# MK_IR_I2C.net
KiCad netlist of a schematic drawn in EasyEDA Pro
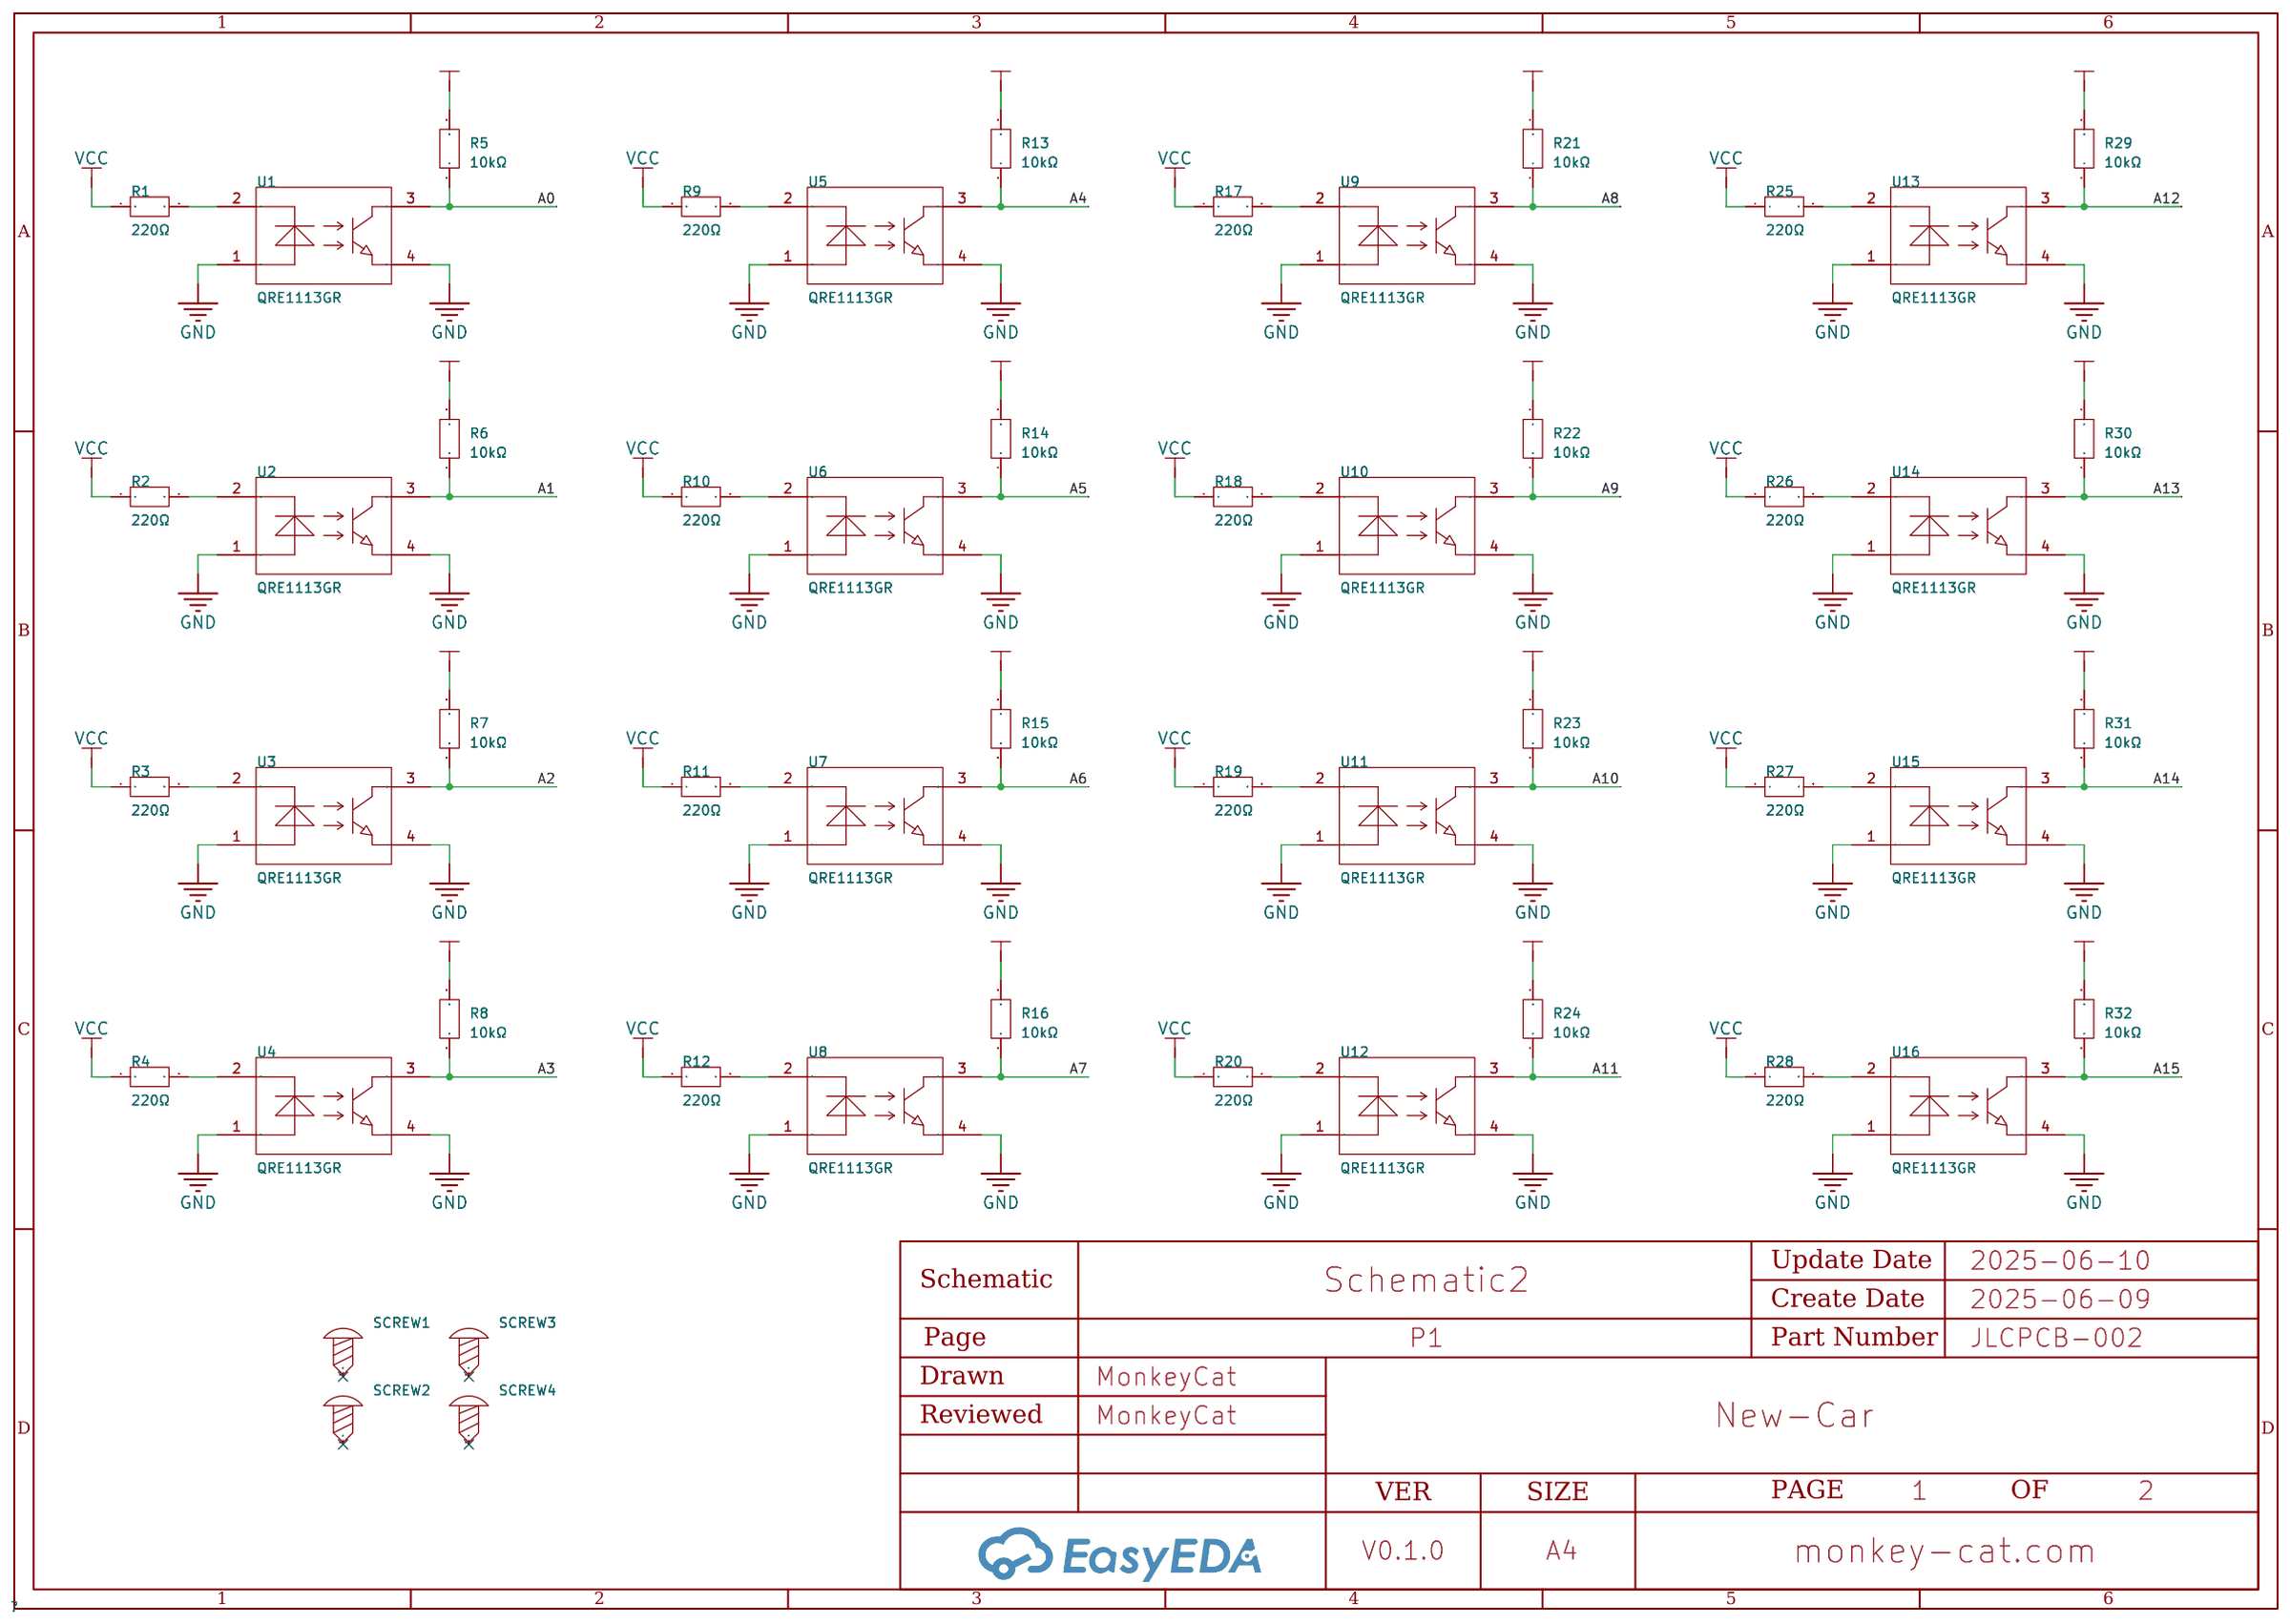
[diagram p0: P1]
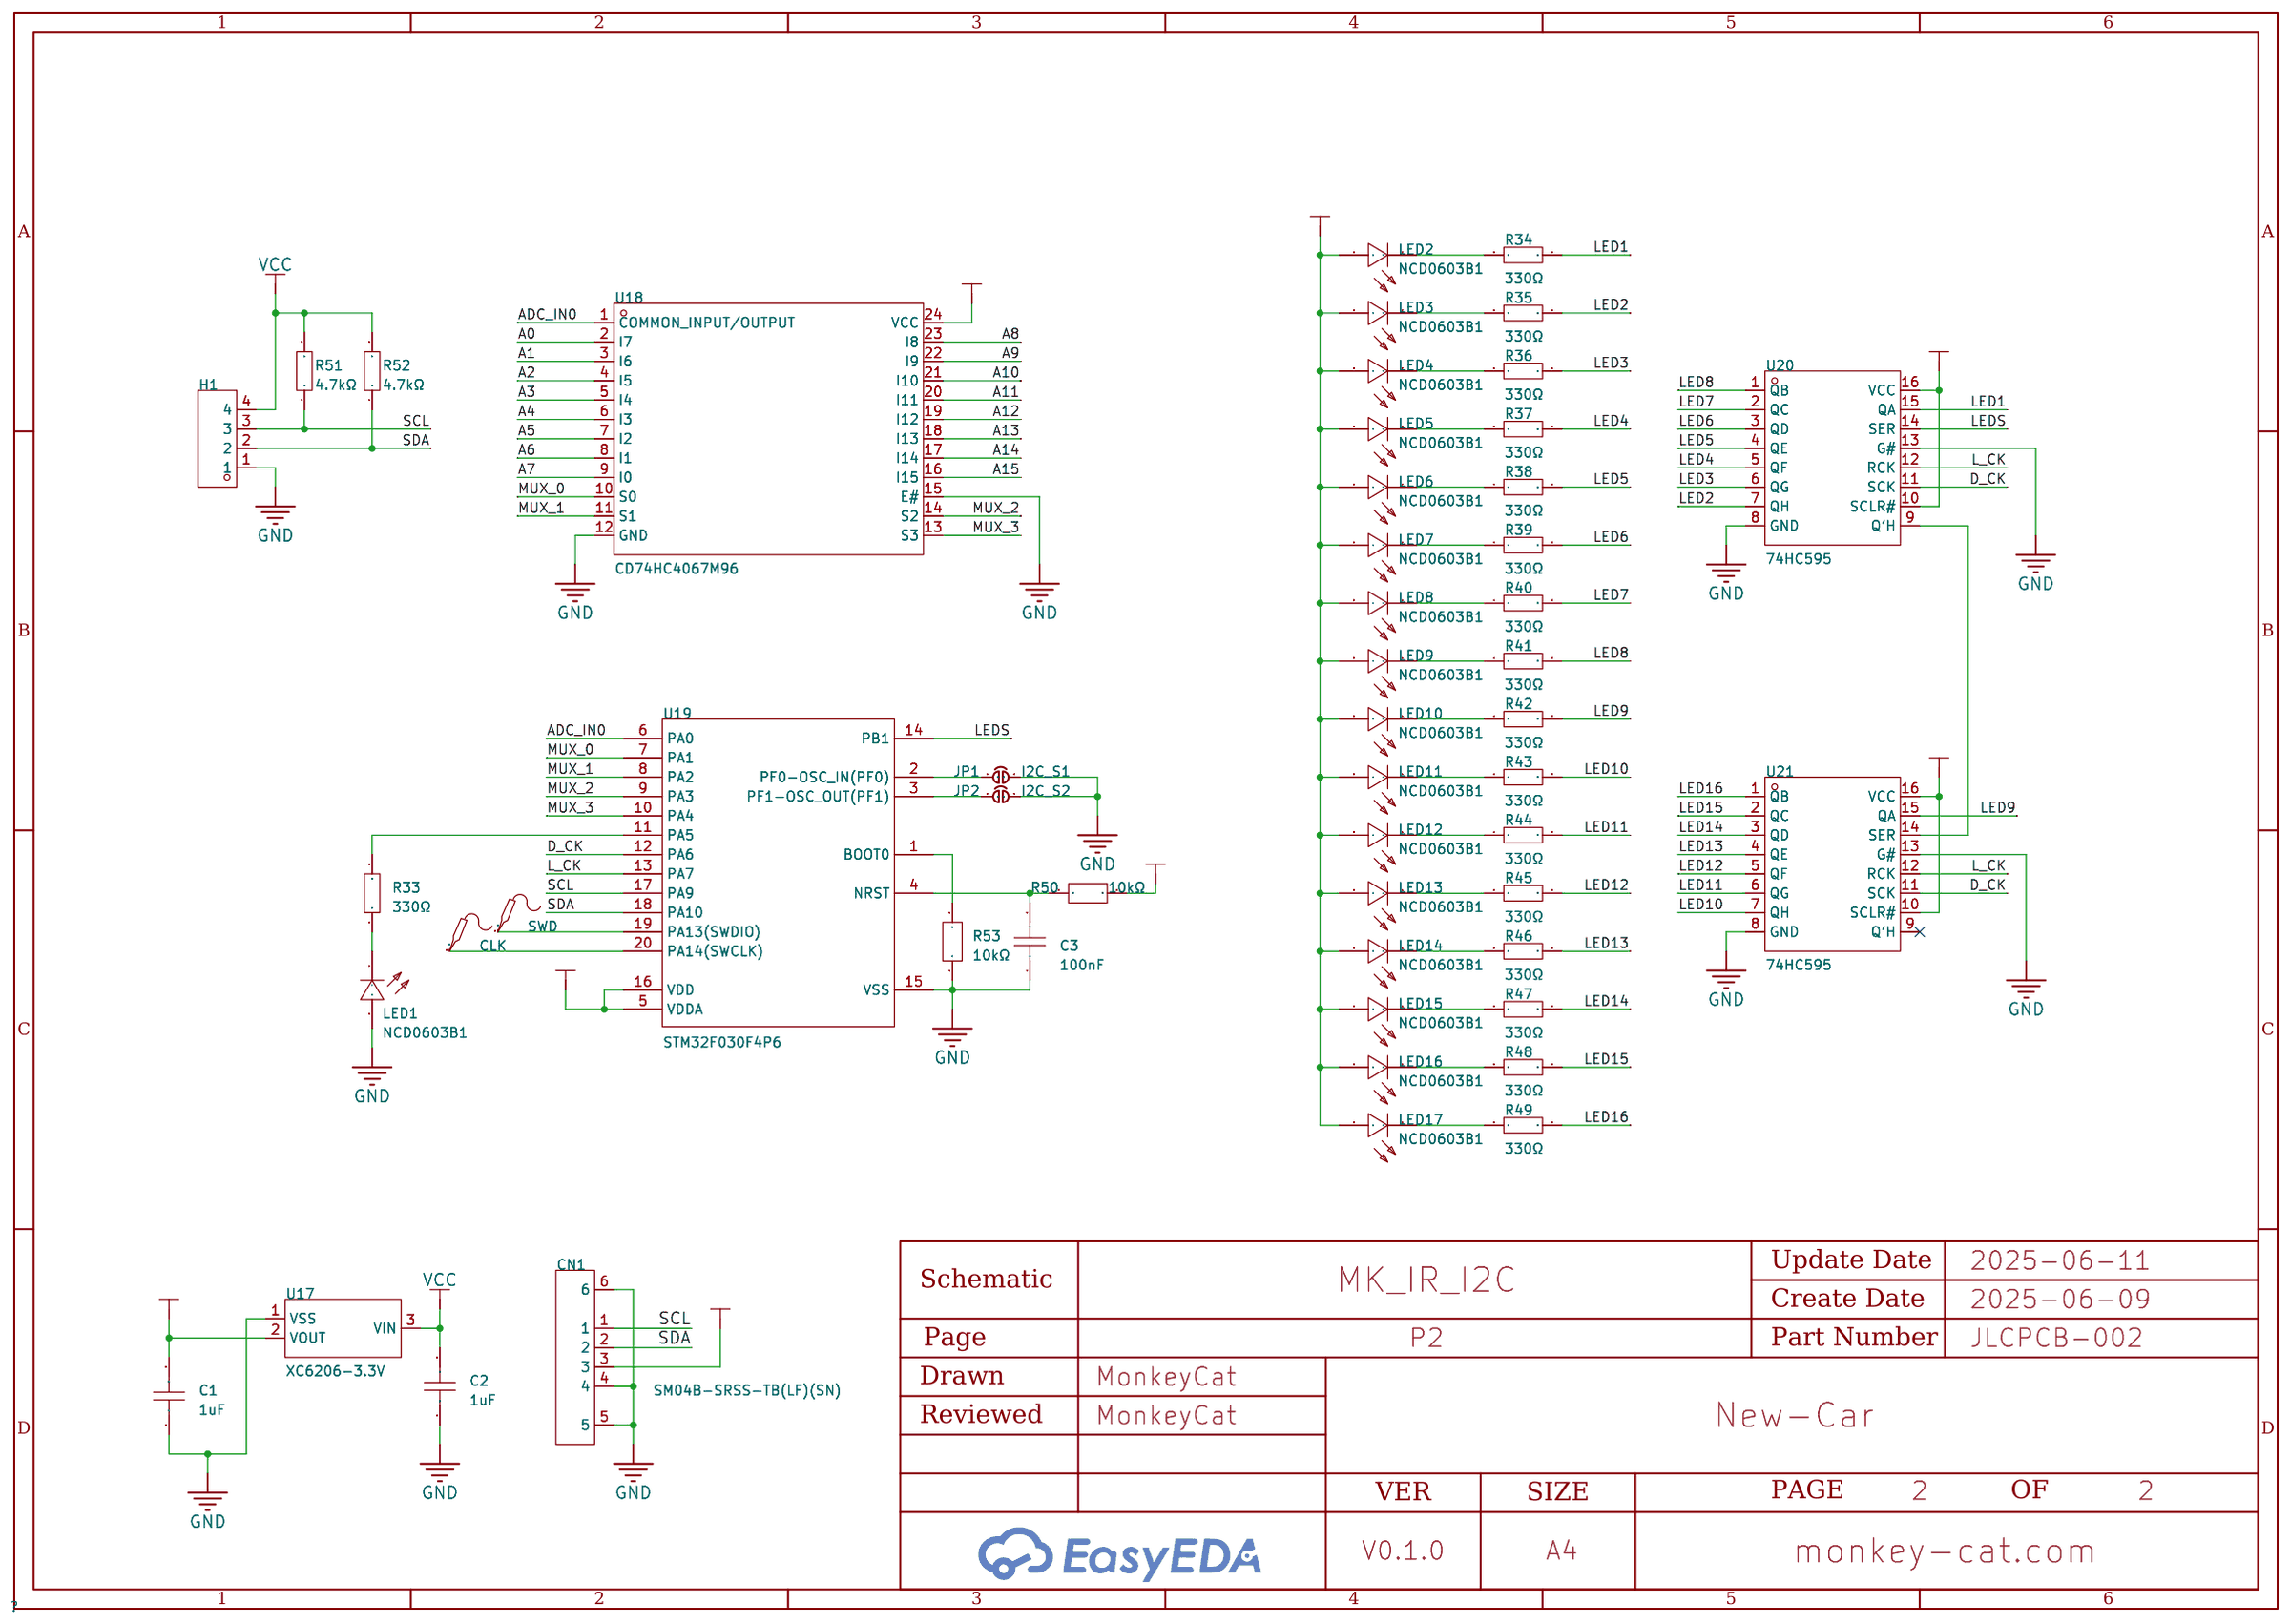
[diagram p1: P2]

(export (version "E")
  (design (tool "Eeschema 10.0.6"))
  (components
    (comp (ref "R1")
      (value "220Ω")
      (footprint "easyedapro:R0603")
      (fields (field (name "Manufacturer Part") "FRC0603F2200TS") (field (name "Manufacturer") "FOJAN(富捷)"))
      (libsource (lib "easyedapro") (part "FRC0603F2200TS"))
    )
    (comp (ref "R2")
      (value "220Ω")
      (footprint "easyedapro:R0603")
      (fields (field (name "Manufacturer Part") "FRC0603F2200TS") (field (name "Manufacturer") "FOJAN(富捷)"))
      (libsource (lib "easyedapro") (part "FRC0603F2200TS"))
    )
    (comp (ref "R3")
      (value "220Ω")
      (footprint "easyedapro:R0603")
      (fields (field (name "Manufacturer Part") "FRC0603F2200TS") (field (name "Manufacturer") "FOJAN(富捷)"))
      (libsource (lib "easyedapro") (part "FRC0603F2200TS"))
    )
    (comp (ref "R4")
      (value "220Ω")
      (footprint "easyedapro:R0603")
      (fields (field (name "Manufacturer Part") "FRC0603F2200TS") (field (name "Manufacturer") "FOJAN(富捷)"))
      (libsource (lib "easyedapro") (part "FRC0603F2200TS"))
    )
    (comp (ref "R5")
      (value "10kΩ")
      (footprint "easyedapro:R0603")
      (fields (field (name "Manufacturer Part") "FRC0603J103 TS") (field (name "Manufacturer") "FOJAN(富捷)"))
      (libsource (lib "easyedapro") (part "FRC0603J103TS"))
    )
    (comp (ref "R6")
      (value "10kΩ")
      (footprint "easyedapro:R0603")
      (fields (field (name "Manufacturer Part") "FRC0603J103 TS") (field (name "Manufacturer") "FOJAN(富捷)"))
      (libsource (lib "easyedapro") (part "FRC0603J103TS"))
    )
    (comp (ref "R7")
      (value "10kΩ")
      (footprint "easyedapro:R0603")
      (fields (field (name "Manufacturer Part") "FRC0603J103 TS") (field (name "Manufacturer") "FOJAN(富捷)"))
      (libsource (lib "easyedapro") (part "FRC0603J103TS"))
    )
    (comp (ref "R8")
      (value "10kΩ")
      (footprint "easyedapro:R0603")
      (fields (field (name "Manufacturer Part") "FRC0603J103 TS") (field (name "Manufacturer") "FOJAN(富捷)"))
      (libsource (lib "easyedapro") (part "FRC0603J103TS"))
    )
    (comp (ref "R9")
      (value "220Ω")
      (footprint "easyedapro:R0603")
      (fields (field (name "Manufacturer Part") "FRC0603F2200TS") (field (name "Manufacturer") "FOJAN(富捷)"))
      (libsource (lib "easyedapro") (part "FRC0603F2200TS"))
    )
    (comp (ref "R10")
      (value "220Ω")
      (footprint "easyedapro:R0603")
      (fields (field (name "Manufacturer Part") "FRC0603F2200TS") (field (name "Manufacturer") "FOJAN(富捷)"))
      (libsource (lib "easyedapro") (part "FRC0603F2200TS"))
    )
    (comp (ref "R11")
      (value "220Ω")
      (footprint "easyedapro:R0603")
      (fields (field (name "Manufacturer Part") "FRC0603F2200TS") (field (name "Manufacturer") "FOJAN(富捷)"))
      (libsource (lib "easyedapro") (part "FRC0603F2200TS"))
    )
    (comp (ref "R12")
      (value "220Ω")
      (footprint "easyedapro:R0603")
      (fields (field (name "Manufacturer Part") "FRC0603F2200TS") (field (name "Manufacturer") "FOJAN(富捷)"))
      (libsource (lib "easyedapro") (part "FRC0603F2200TS"))
    )
    (comp (ref "R13")
      (value "10kΩ")
      (footprint "easyedapro:R0603")
      (fields (field (name "Manufacturer Part") "FRC0603J103 TS") (field (name "Manufacturer") "FOJAN(富捷)"))
      (libsource (lib "easyedapro") (part "FRC0603J103TS"))
    )
    (comp (ref "R14")
      (value "10kΩ")
      (footprint "easyedapro:R0603")
      (fields (field (name "Manufacturer Part") "FRC0603J103 TS") (field (name "Manufacturer") "FOJAN(富捷)"))
      (libsource (lib "easyedapro") (part "FRC0603J103TS"))
    )
    (comp (ref "R15")
      (value "10kΩ")
      (footprint "easyedapro:R0603")
      (fields (field (name "Manufacturer Part") "FRC0603J103 TS") (field (name "Manufacturer") "FOJAN(富捷)"))
      (libsource (lib "easyedapro") (part "FRC0603J103TS"))
    )
    (comp (ref "R16")
      (value "10kΩ")
      (footprint "easyedapro:R0603")
      (fields (field (name "Manufacturer Part") "FRC0603J103 TS") (field (name "Manufacturer") "FOJAN(富捷)"))
      (libsource (lib "easyedapro") (part "FRC0603J103TS"))
    )
    (comp (ref "R17")
      (value "220Ω")
      (footprint "easyedapro:R0603")
      (fields (field (name "Manufacturer Part") "FRC0603F2200TS") (field (name "Manufacturer") "FOJAN(富捷)"))
      (libsource (lib "easyedapro") (part "FRC0603F2200TS"))
    )
    (comp (ref "R18")
      (value "220Ω")
      (footprint "easyedapro:R0603")
      (fields (field (name "Manufacturer Part") "FRC0603F2200TS") (field (name "Manufacturer") "FOJAN(富捷)"))
      (libsource (lib "easyedapro") (part "FRC0603F2200TS"))
    )
    (comp (ref "R19")
      (value "220Ω")
      (footprint "easyedapro:R0603")
      (fields (field (name "Manufacturer Part") "FRC0603F2200TS") (field (name "Manufacturer") "FOJAN(富捷)"))
      (libsource (lib "easyedapro") (part "FRC0603F2200TS"))
    )
    (comp (ref "R20")
      (value "220Ω")
      (footprint "easyedapro:R0603")
      (fields (field (name "Manufacturer Part") "FRC0603F2200TS") (field (name "Manufacturer") "FOJAN(富捷)"))
      (libsource (lib "easyedapro") (part "FRC0603F2200TS"))
    )
    (comp (ref "R21")
      (value "10kΩ")
      (footprint "easyedapro:R0603")
      (fields (field (name "Manufacturer Part") "FRC0603J103 TS") (field (name "Manufacturer") "FOJAN(富捷)"))
      (libsource (lib "easyedapro") (part "FRC0603J103TS"))
    )
    (comp (ref "R22")
      (value "10kΩ")
      (footprint "easyedapro:R0603")
      (fields (field (name "Manufacturer Part") "FRC0603J103 TS") (field (name "Manufacturer") "FOJAN(富捷)"))
      (libsource (lib "easyedapro") (part "FRC0603J103TS"))
    )
    (comp (ref "R23")
      (value "10kΩ")
      (footprint "easyedapro:R0603")
      (fields (field (name "Manufacturer Part") "FRC0603J103 TS") (field (name "Manufacturer") "FOJAN(富捷)"))
      (libsource (lib "easyedapro") (part "FRC0603J103TS"))
    )
    (comp (ref "R24")
      (value "10kΩ")
      (footprint "easyedapro:R0603")
      (fields (field (name "Manufacturer Part") "FRC0603J103 TS") (field (name "Manufacturer") "FOJAN(富捷)"))
      (libsource (lib "easyedapro") (part "FRC0603J103TS"))
    )
    (comp (ref "R25")
      (value "220Ω")
      (footprint "easyedapro:R0603")
      (fields (field (name "Manufacturer Part") "FRC0603F2200TS") (field (name "Manufacturer") "FOJAN(富捷)"))
      (libsource (lib "easyedapro") (part "FRC0603F2200TS"))
    )
    (comp (ref "R26")
      (value "220Ω")
      (footprint "easyedapro:R0603")
      (fields (field (name "Manufacturer Part") "FRC0603F2200TS") (field (name "Manufacturer") "FOJAN(富捷)"))
      (libsource (lib "easyedapro") (part "FRC0603F2200TS"))
    )
    (comp (ref "R27")
      (value "220Ω")
      (footprint "easyedapro:R0603")
      (fields (field (name "Manufacturer Part") "FRC0603F2200TS") (field (name "Manufacturer") "FOJAN(富捷)"))
      (libsource (lib "easyedapro") (part "FRC0603F2200TS"))
    )
    (comp (ref "R28")
      (value "220Ω")
      (footprint "easyedapro:R0603")
      (fields (field (name "Manufacturer Part") "FRC0603F2200TS") (field (name "Manufacturer") "FOJAN(富捷)"))
      (libsource (lib "easyedapro") (part "FRC0603F2200TS"))
    )
    (comp (ref "R29")
      (value "10kΩ")
      (footprint "easyedapro:R0603")
      (fields (field (name "Manufacturer Part") "FRC0603J103 TS") (field (name "Manufacturer") "FOJAN(富捷)"))
      (libsource (lib "easyedapro") (part "FRC0603J103TS"))
    )
    (comp (ref "R30")
      (value "10kΩ")
      (footprint "easyedapro:R0603")
      (fields (field (name "Manufacturer Part") "FRC0603J103 TS") (field (name "Manufacturer") "FOJAN(富捷)"))
      (libsource (lib "easyedapro") (part "FRC0603J103TS"))
    )
    (comp (ref "R31")
      (value "10kΩ")
      (footprint "easyedapro:R0603")
      (fields (field (name "Manufacturer Part") "FRC0603J103 TS") (field (name "Manufacturer") "FOJAN(富捷)"))
      (libsource (lib "easyedapro") (part "FRC0603J103TS"))
    )
    (comp (ref "R32")
      (value "10kΩ")
      (footprint "easyedapro:R0603")
      (fields (field (name "Manufacturer Part") "FRC0603J103 TS") (field (name "Manufacturer") "FOJAN(富捷)"))
      (libsource (lib "easyedapro") (part "FRC0603J103TS"))
    )
    (comp (ref "SCREW1")
      (value "~")
      (footprint "easyedapro:Screw-Hole-M3")
      (libsource (lib "easyedapro") (part "Screw-Hole"))
    )
    (comp (ref "SCREW2")
      (value "~")
      (footprint "easyedapro:Screw-Hole-M3")
      (libsource (lib "easyedapro") (part "Screw-Hole"))
    )
    (comp (ref "SCREW3")
      (value "~")
      (footprint "easyedapro:Screw-Hole-M3")
      (libsource (lib "easyedapro") (part "Screw-Hole"))
    )
    (comp (ref "SCREW4")
      (value "~")
      (footprint "easyedapro:Screw-Hole-M3")
      (libsource (lib "easyedapro") (part "Screw-Hole"))
    )
    (comp (ref "U1")
      (value "QRE1113GR")
      (footprint "easyedapro:OPTO-SMD_QRE1113GR")
      (description "Sensing Distance:1mm Collector Current (Max):20mA")
      (fields (field (name "Manufacturer") "onsemi(安森美)"))
      (libsource (lib "easyedapro") (part "QRE1113GR"))
    )
    (comp (ref "U2")
      (value "QRE1113GR")
      (footprint "easyedapro:OPTO-SMD_QRE1113GR")
      (description "Sensing Distance:1mm Collector Current (Max):20mA")
      (fields (field (name "Manufacturer") "onsemi(安森美)"))
      (libsource (lib "easyedapro") (part "QRE1113GR"))
    )
    (comp (ref "U3")
      (value "QRE1113GR")
      (footprint "easyedapro:OPTO-SMD_QRE1113GR")
      (description "Sensing Distance:1mm Collector Current (Max):20mA")
      (fields (field (name "Manufacturer") "onsemi(安森美)"))
      (libsource (lib "easyedapro") (part "QRE1113GR"))
    )
    (comp (ref "U4")
      (value "QRE1113GR")
      (footprint "easyedapro:OPTO-SMD_QRE1113GR")
      (description "Sensing Distance:1mm Collector Current (Max):20mA")
      (fields (field (name "Manufacturer") "onsemi(安森美)"))
      (libsource (lib "easyedapro") (part "QRE1113GR"))
    )
    (comp (ref "U5")
      (value "QRE1113GR")
      (footprint "easyedapro:OPTO-SMD_QRE1113GR")
      (description "Sensing Distance:1mm Collector Current (Max):20mA")
      (fields (field (name "Manufacturer") "onsemi(安森美)"))
      (libsource (lib "easyedapro") (part "QRE1113GR"))
    )
    (comp (ref "U6")
      (value "QRE1113GR")
      (footprint "easyedapro:OPTO-SMD_QRE1113GR")
      (description "Sensing Distance:1mm Collector Current (Max):20mA")
      (fields (field (name "Manufacturer") "onsemi(安森美)"))
      (libsource (lib "easyedapro") (part "QRE1113GR"))
    )
    (comp (ref "U7")
      (value "QRE1113GR")
      (footprint "easyedapro:OPTO-SMD_QRE1113GR")
      (description "Sensing Distance:1mm Collector Current (Max):20mA")
      (fields (field (name "Manufacturer") "onsemi(安森美)"))
      (libsource (lib "easyedapro") (part "QRE1113GR"))
    )
    (comp (ref "U8")
      (value "QRE1113GR")
      (footprint "easyedapro:OPTO-SMD_QRE1113GR")
      (description "Sensing Distance:1mm Collector Current (Max):20mA")
      (fields (field (name "Manufacturer") "onsemi(安森美)"))
      (libsource (lib "easyedapro") (part "QRE1113GR"))
    )
    (comp (ref "U9")
      (value "QRE1113GR")
      (footprint "easyedapro:OPTO-SMD_QRE1113GR")
      (description "Sensing Distance:1mm Collector Current (Max):20mA")
      (fields (field (name "Manufacturer") "onsemi(安森美)"))
      (libsource (lib "easyedapro") (part "QRE1113GR"))
    )
    (comp (ref "U10")
      (value "QRE1113GR")
      (footprint "easyedapro:OPTO-SMD_QRE1113GR")
      (description "Sensing Distance:1mm Collector Current (Max):20mA")
      (fields (field (name "Manufacturer") "onsemi(安森美)"))
      (libsource (lib "easyedapro") (part "QRE1113GR"))
    )
    (comp (ref "U11")
      (value "QRE1113GR")
      (footprint "easyedapro:OPTO-SMD_QRE1113GR")
      (description "Sensing Distance:1mm Collector Current (Max):20mA")
      (fields (field (name "Manufacturer") "onsemi(安森美)"))
      (libsource (lib "easyedapro") (part "QRE1113GR"))
    )
    (comp (ref "U12")
      (value "QRE1113GR")
      (footprint "easyedapro:OPTO-SMD_QRE1113GR")
      (description "Sensing Distance:1mm Collector Current (Max):20mA")
      (fields (field (name "Manufacturer") "onsemi(安森美)"))
      (libsource (lib "easyedapro") (part "QRE1113GR"))
    )
    (comp (ref "U13")
      (value "QRE1113GR")
      (footprint "easyedapro:OPTO-SMD_QRE1113GR")
      (description "Sensing Distance:1mm Collector Current (Max):20mA")
      (fields (field (name "Manufacturer") "onsemi(安森美)"))
      (libsource (lib "easyedapro") (part "QRE1113GR"))
    )
    (comp (ref "U14")
      (value "QRE1113GR")
      (footprint "easyedapro:OPTO-SMD_QRE1113GR")
      (description "Sensing Distance:1mm Collector Current (Max):20mA")
      (fields (field (name "Manufacturer") "onsemi(安森美)"))
      (libsource (lib "easyedapro") (part "QRE1113GR"))
    )
    (comp (ref "U15")
      (value "QRE1113GR")
      (footprint "easyedapro:OPTO-SMD_QRE1113GR")
      (description "Sensing Distance:1mm Collector Current (Max):20mA")
      (fields (field (name "Manufacturer") "onsemi(安森美)"))
      (libsource (lib "easyedapro") (part "QRE1113GR"))
    )
    (comp (ref "U16")
      (value "QRE1113GR")
      (footprint "easyedapro:OPTO-SMD_QRE1113GR")
      (description "Sensing Distance:1mm Collector Current (Max):20mA")
      (fields (field (name "Manufacturer") "onsemi(安森美)"))
      (libsource (lib "easyedapro") (part "QRE1113GR"))
    )
    (comp (ref "C1")
      (value "1uF")
      (footprint "easyedapro:C0603")
      (fields
        (field (name "Manufacturer Part") "CL10A105KB8NNNC")
        (field (name "Manufacturer") "SAMSUNG(三星)")
      )
      (libsource (lib "easyedapro") (part "CL10A105KB8NNNC"))
    )
    (comp (ref "C2")
      (value "1uF")
      (footprint "easyedapro:C0603")
      (fields
        (field (name "Manufacturer Part") "CL10A105KB8NNNC")
        (field (name "Manufacturer") "SAMSUNG(三星)")
      )
      (libsource (lib "easyedapro") (part "CL10A105KB8NNNC"))
    )
    (comp (ref "C3")
      (value "100nF")
      (footprint "easyedapro:C0603")
      (fields
        (field (name "Manufacturer Part") "CC0603KRX7R9BB104")
        (field (name "Manufacturer") "YAGEO(国巨)")
      )
      (libsource (lib "easyedapro") (part "CC0603KRX7R9BB104"))
    )
    (comp (ref "CLK")
      (value "~")
      (footprint "easyedapro:Test-Point-0.5mm")
      (description "Test Point 测试点")
      (libsource (lib "easyedapro") (part "Test-Point"))
    )
    (comp (ref "CN1")
      (value "SM04B-SRSS-TB(LF)(SN)")
      (footprint "easyedapro:CONN-SMD_4P-P1.00_SM04B-SRSS-TB-LF-SN")
      (fields (field (name "Manufacturer") "JST"))
      (libsource (lib "easyedapro") (part "SM04B-SRSS-TB (LF)(SN)"))
    )
    (comp (ref "H1")
      (value "~")
      (footprint "easyedapro:HDR-TH_4P-P2.54-V-M")
      (libsource (lib "easyedapro") (part "PZ254V-11-04P"))
    )
    (comp (ref "JP1")
      (value "I2C_S1")
      (footprint "easyedapro:SOLDER JUMPER")
      (libsource (lib "easyedapro") (part "Solder Jumper"))
    )
    (comp (ref "JP2")
      (value "I2C_S2")
      (footprint "easyedapro:SOLDER JUMPER")
      (libsource (lib "easyedapro") (part "Solder Jumper"))
    )
    (comp (ref "LED1")
      (value "NCD0603B1")
      (footprint "easyedapro:LED0603-RD")
      (fields (field (name "Manufacturer") "国星光电"))
      (libsource (lib "easyedapro") (part "FC-DA1608BK-470H10"))
    )
    (comp (ref "LED2")
      (value "NCD0603B1")
      (footprint "easyedapro:LED0603-RD")
      (fields (field (name "Manufacturer") "国星光电"))
      (libsource (lib "easyedapro") (part "FC-DA1608BK-470H10"))
    )
    (comp (ref "LED3")
      (value "NCD0603B1")
      (footprint "easyedapro:LED0603-RD")
      (fields (field (name "Manufacturer") "国星光电"))
      (libsource (lib "easyedapro") (part "FC-DA1608BK-470H10"))
    )
    (comp (ref "LED4")
      (value "NCD0603B1")
      (footprint "easyedapro:LED0603-RD")
      (fields (field (name "Manufacturer") "国星光电"))
      (libsource (lib "easyedapro") (part "FC-DA1608BK-470H10"))
    )
    (comp (ref "LED5")
      (value "NCD0603B1")
      (footprint "easyedapro:LED0603-RD")
      (fields (field (name "Manufacturer") "国星光电"))
      (libsource (lib "easyedapro") (part "FC-DA1608BK-470H10"))
    )
    (comp (ref "LED6")
      (value "NCD0603B1")
      (footprint "easyedapro:LED0603-RD")
      (fields (field (name "Manufacturer") "国星光电"))
      (libsource (lib "easyedapro") (part "FC-DA1608BK-470H10"))
    )
    (comp (ref "LED7")
      (value "NCD0603B1")
      (footprint "easyedapro:LED0603-RD")
      (fields (field (name "Manufacturer") "国星光电"))
      (libsource (lib "easyedapro") (part "FC-DA1608BK-470H10"))
    )
    (comp (ref "LED8")
      (value "NCD0603B1")
      (footprint "easyedapro:LED0603-RD")
      (fields (field (name "Manufacturer") "国星光电"))
      (libsource (lib "easyedapro") (part "FC-DA1608BK-470H10"))
    )
    (comp (ref "LED9")
      (value "NCD0603B1")
      (footprint "easyedapro:LED0603-RD")
      (fields (field (name "Manufacturer") "国星光电"))
      (libsource (lib "easyedapro") (part "FC-DA1608BK-470H10"))
    )
    (comp (ref "LED10")
      (value "NCD0603B1")
      (footprint "easyedapro:LED0603-RD")
      (fields (field (name "Manufacturer") "国星光电"))
      (libsource (lib "easyedapro") (part "FC-DA1608BK-470H10"))
    )
    (comp (ref "LED11")
      (value "NCD0603B1")
      (footprint "easyedapro:LED0603-RD")
      (fields (field (name "Manufacturer") "国星光电"))
      (libsource (lib "easyedapro") (part "FC-DA1608BK-470H10"))
    )
    (comp (ref "LED12")
      (value "NCD0603B1")
      (footprint "easyedapro:LED0603-RD")
      (fields (field (name "Manufacturer") "国星光电"))
      (libsource (lib "easyedapro") (part "FC-DA1608BK-470H10"))
    )
    (comp (ref "LED13")
      (value "NCD0603B1")
      (footprint "easyedapro:LED0603-RD")
      (fields (field (name "Manufacturer") "国星光电"))
      (libsource (lib "easyedapro") (part "FC-DA1608BK-470H10"))
    )
    (comp (ref "LED14")
      (value "NCD0603B1")
      (footprint "easyedapro:LED0603-RD")
      (fields (field (name "Manufacturer") "国星光电"))
      (libsource (lib "easyedapro") (part "FC-DA1608BK-470H10"))
    )
    (comp (ref "LED15")
      (value "NCD0603B1")
      (footprint "easyedapro:LED0603-RD")
      (fields (field (name "Manufacturer") "国星光电"))
      (libsource (lib "easyedapro") (part "FC-DA1608BK-470H10"))
    )
    (comp (ref "LED16")
      (value "NCD0603B1")
      (footprint "easyedapro:LED0603-RD")
      (fields (field (name "Manufacturer") "国星光电"))
      (libsource (lib "easyedapro") (part "FC-DA1608BK-470H10"))
    )
    (comp (ref "LED17")
      (value "NCD0603B1")
      (footprint "easyedapro:LED0603-RD")
      (fields (field (name "Manufacturer") "国星光电"))
      (libsource (lib "easyedapro") (part "FC-DA1608BK-470H10"))
    )
    (comp (ref "R33")
      (value "330Ω")
      (footprint "easyedapro:R0603")
      (fields
        (field (name "Manufacturer Part") "0603WAF3300T5E")
        (field (name "Manufacturer") "UNI-ROYAL(厚声)")
      )
      (libsource (lib "easyedapro") (part "0603WAF3300T5E"))
    )
    (comp (ref "R34")
      (value "330Ω")
      (footprint "easyedapro:R0603")
      (fields
        (field (name "Manufacturer Part") "0603WAF3300T5E")
        (field (name "Manufacturer") "UNI-ROYAL(厚声)")
      )
      (libsource (lib "easyedapro") (part "0603WAF3300T5E"))
    )
    (comp (ref "R35")
      (value "330Ω")
      (footprint "easyedapro:R0603")
      (fields
        (field (name "Manufacturer Part") "0603WAF3300T5E")
        (field (name "Manufacturer") "UNI-ROYAL(厚声)")
      )
      (libsource (lib "easyedapro") (part "0603WAF3300T5E"))
    )
    (comp (ref "R36")
      (value "330Ω")
      (footprint "easyedapro:R0603")
      (fields
        (field (name "Manufacturer Part") "0603WAF3300T5E")
        (field (name "Manufacturer") "UNI-ROYAL(厚声)")
      )
      (libsource (lib "easyedapro") (part "0603WAF3300T5E"))
    )
    (comp (ref "R37")
      (value "330Ω")
      (footprint "easyedapro:R0603")
      (fields
        (field (name "Manufacturer Part") "0603WAF3300T5E")
        (field (name "Manufacturer") "UNI-ROYAL(厚声)")
      )
      (libsource (lib "easyedapro") (part "0603WAF3300T5E"))
    )
    (comp (ref "R38")
      (value "330Ω")
      (footprint "easyedapro:R0603")
      (fields
        (field (name "Manufacturer Part") "0603WAF3300T5E")
        (field (name "Manufacturer") "UNI-ROYAL(厚声)")
      )
      (libsource (lib "easyedapro") (part "0603WAF3300T5E"))
    )
    (comp (ref "R39")
      (value "330Ω")
      (footprint "easyedapro:R0603")
      (fields
        (field (name "Manufacturer Part") "0603WAF3300T5E")
        (field (name "Manufacturer") "UNI-ROYAL(厚声)")
      )
      (libsource (lib "easyedapro") (part "0603WAF3300T5E"))
    )
    (comp (ref "R40")
      (value "330Ω")
      (footprint "easyedapro:R0603")
      (fields
        (field (name "Manufacturer Part") "0603WAF3300T5E")
        (field (name "Manufacturer") "UNI-ROYAL(厚声)")
      )
      (libsource (lib "easyedapro") (part "0603WAF3300T5E"))
    )
    (comp (ref "R41")
      (value "330Ω")
      (footprint "easyedapro:R0603")
      (fields
        (field (name "Manufacturer Part") "0603WAF3300T5E")
        (field (name "Manufacturer") "UNI-ROYAL(厚声)")
      )
      (libsource (lib "easyedapro") (part "0603WAF3300T5E"))
    )
    (comp (ref "R42")
      (value "330Ω")
      (footprint "easyedapro:R0603")
      (fields
        (field (name "Manufacturer Part") "0603WAF3300T5E")
        (field (name "Manufacturer") "UNI-ROYAL(厚声)")
      )
      (libsource (lib "easyedapro") (part "0603WAF3300T5E"))
    )
    (comp (ref "R43")
      (value "330Ω")
      (footprint "easyedapro:R0603")
      (fields
        (field (name "Manufacturer Part") "0603WAF3300T5E")
        (field (name "Manufacturer") "UNI-ROYAL(厚声)")
      )
      (libsource (lib "easyedapro") (part "0603WAF3300T5E"))
    )
    (comp (ref "R44")
      (value "330Ω")
      (footprint "easyedapro:R0603")
      (fields
        (field (name "Manufacturer Part") "0603WAF3300T5E")
        (field (name "Manufacturer") "UNI-ROYAL(厚声)")
      )
      (libsource (lib "easyedapro") (part "0603WAF3300T5E"))
    )
    (comp (ref "R45")
      (value "330Ω")
      (footprint "easyedapro:R0603")
      (fields
        (field (name "Manufacturer Part") "0603WAF3300T5E")
        (field (name "Manufacturer") "UNI-ROYAL(厚声)")
      )
      (libsource (lib "easyedapro") (part "0603WAF3300T5E"))
    )
    (comp (ref "R46")
      (value "330Ω")
      (footprint "easyedapro:R0603")
      (fields
        (field (name "Manufacturer Part") "0603WAF3300T5E")
        (field (name "Manufacturer") "UNI-ROYAL(厚声)")
      )
      (libsource (lib "easyedapro") (part "0603WAF3300T5E"))
    )
    (comp (ref "R47")
      (value "330Ω")
      (footprint "easyedapro:R0603")
      (fields
        (field (name "Manufacturer Part") "0603WAF3300T5E")
        (field (name "Manufacturer") "UNI-ROYAL(厚声)")
      )
      (libsource (lib "easyedapro") (part "0603WAF3300T5E"))
    )
    (comp (ref "R48")
      (value "330Ω")
      (footprint "easyedapro:R0603")
      (fields
        (field (name "Manufacturer Part") "0603WAF3300T5E")
        (field (name "Manufacturer") "UNI-ROYAL(厚声)")
      )
      (libsource (lib "easyedapro") (part "0603WAF3300T5E"))
    )
    (comp (ref "R49")
      (value "330Ω")
      (footprint "easyedapro:R0603")
      (fields
        (field (name "Manufacturer Part") "0603WAF3300T5E")
        (field (name "Manufacturer") "UNI-ROYAL(厚声)")
      )
      (libsource (lib "easyedapro") (part "0603WAF3300T5E"))
    )
    (comp (ref "R50")
      (value "10kΩ")
      (footprint "easyedapro:R0603")
      (fields (field (name "Manufacturer Part") "FRC0603J103 TS") (field (name "Manufacturer") "FOJAN(富捷)"))
      (libsource (lib "easyedapro") (part "FRC0603J103TS"))
    )
    (comp (ref "R51")
      (value "4.7kΩ")
      (footprint "easyedapro:R0603")
      (fields (field (name "Manufacturer Part") "RC0603FR-074K7L") (field (name "Manufacturer") "YAGEO(国巨)"))
      (libsource (lib "easyedapro") (part "RC0603FR-074K7L"))
    )
    (comp (ref "R52")
      (value "4.7kΩ")
      (footprint "easyedapro:R0603")
      (fields (field (name "Manufacturer Part") "RC0603FR-074K7L") (field (name "Manufacturer") "YAGEO(国巨)"))
      (libsource (lib "easyedapro") (part "RC0603FR-074K7L"))
    )
    (comp (ref "R53")
      (value "10kΩ")
      (footprint "easyedapro:R0603")
      (fields (field (name "Manufacturer Part") "FRC0603J103 TS") (field (name "Manufacturer") "FOJAN(富捷)"))
      (libsource (lib "easyedapro") (part "FRC0603J103TS"))
    )
    (comp (ref "SWD")
      (value "~")
      (footprint "easyedapro:Test-Point-0.5mm")
      (description "Test Point 测试点")
      (libsource (lib "easyedapro") (part "Test-Point"))
    )
    (comp (ref "U17")
      (value "XC6206-3.3V")
      (footprint "easyedapro:SOT-23-3_L2.9-W1.3-P0.95-LS2.4-BR")
      (fields (field (name "Manufacturer") "YONGYUTAI(永裕泰)"))
      (libsource (lib "easyedapro") (part "XC6206-3.3V_C3015484"))
    )
    (comp (ref "U18")
      (value "CD74HC4067M96")
      (footprint "easyedapro:SOIC-24_L15.4-W7.5-P1.27-LS10.3-BL")
      (fields (field (name "Manufacturer") "TI(德州仪器)"))
      (libsource (lib "easyedapro") (part "CD74HC4067M96"))
    )
    (comp (ref "U19")
      (value "STM32F030F4P6")
      (footprint "easyedapro:TSSOP-20_L6.5-W4.4-P0.65-LS6.4-BL")
      (fields (field (name "Manufacturer") "ST(意法半导体)"))
      (libsource (lib "easyedapro") (part "STM32F030F4P6"))
    )
    (comp (ref "U20")
      (value "74HC595")
      (footprint "easyedapro:SOP-16_L9.9-W3.9-P1.27-LS6.0-BL")
      (fields (field (name "Manufacturer") "GR(国睿)"))
      (libsource (lib "easyedapro") (part "74HC595"))
    )
    (comp (ref "U21")
      (value "74HC595")
      (footprint "easyedapro:SOP-16_L9.9-W3.9-P1.27-LS6.0-BL")
      (fields (field (name "Manufacturer") "GR(国睿)"))
      (libsource (lib "easyedapro") (part "74HC595"))
    )
  )
  (nets
    (net (code "1") (name "+3V3") (class "Default")
      (node (ref "C1") (pin "2") (pinfunction "2_2") (pintype "unspecified"))
      (node (ref "LED10") (pin "2") (pinfunction "+_2") (pintype "input"))
      (node (ref "LED11") (pin "2") (pinfunction "+_2") (pintype "input"))
      (node (ref "LED12") (pin "2") (pinfunction "+_2") (pintype "input"))
      (node (ref "LED13") (pin "2") (pinfunction "+_2") (pintype "input"))
      (node (ref "LED14") (pin "2") (pinfunction "+_2") (pintype "input"))
      (node (ref "LED15") (pin "2") (pinfunction "+_2") (pintype "input"))
      (node (ref "LED16") (pin "2") (pinfunction "+_2") (pintype "input"))
      (node (ref "LED17") (pin "2") (pinfunction "+_2") (pintype "input"))
      (node (ref "LED2") (pin "2") (pinfunction "+_2") (pintype "input"))
      (node (ref "LED3") (pin "2") (pinfunction "+_2") (pintype "input"))
      (node (ref "LED4") (pin "2") (pinfunction "+_2") (pintype "input"))
      (node (ref "LED5") (pin "2") (pinfunction "+_2") (pintype "input"))
      (node (ref "LED6") (pin "2") (pinfunction "+_2") (pintype "input"))
      (node (ref "LED7") (pin "2") (pinfunction "+_2") (pintype "input"))
      (node (ref "LED8") (pin "2") (pinfunction "+_2") (pintype "input"))
      (node (ref "LED9") (pin "2") (pinfunction "+_2") (pintype "input"))
      (node (ref "R13") (pin "2") (pinfunction "2_2") (pintype "unspecified"))
      (node (ref "R14") (pin "2") (pinfunction "2_2") (pintype "unspecified"))
      (node (ref "R15") (pin "2") (pinfunction "2_2") (pintype "unspecified"))
      (node (ref "R16") (pin "2") (pinfunction "2_2") (pintype "unspecified"))
      (node (ref "R21") (pin "2") (pinfunction "2_2") (pintype "unspecified"))
      (node (ref "R22") (pin "2") (pinfunction "2_2") (pintype "unspecified"))
      (node (ref "R23") (pin "2") (pinfunction "2_2") (pintype "unspecified"))
      (node (ref "R24") (pin "2") (pinfunction "2_2") (pintype "unspecified"))
      (node (ref "R29") (pin "2") (pinfunction "2_2") (pintype "unspecified"))
      (node (ref "R30") (pin "2") (pinfunction "2_2") (pintype "unspecified"))
      (node (ref "R31") (pin "2") (pinfunction "2_2") (pintype "unspecified"))
      (node (ref "R32") (pin "2") (pinfunction "2_2") (pintype "unspecified"))
      (node (ref "R5") (pin "2") (pinfunction "2_2") (pintype "unspecified"))
      (node (ref "R50") (pin "2") (pinfunction "2_2") (pintype "unspecified"))
      (node (ref "R6") (pin "2") (pinfunction "2_2") (pintype "unspecified"))
      (node (ref "R7") (pin "2") (pinfunction "2_2") (pintype "unspecified"))
      (node (ref "R8") (pin "2") (pinfunction "2_2") (pintype "unspecified"))
      (node (ref "U17") (pin "2") (pinfunction "VOUT_2") (pintype "unspecified"))
      (node (ref "U18") (pin "24") (pinfunction "VCC_24") (pintype "unspecified"))
      (node (ref "U19") (pin "16") (pinfunction "VDD_16") (pintype "unspecified"))
      (node (ref "U19") (pin "5") (pinfunction "VDDA_5") (pintype "unspecified"))
      (node (ref "U20") (pin "10") (pinfunction "SCLR#_10") (pintype "unspecified"))
      (node (ref "U20") (pin "16") (pinfunction "VCC_16") (pintype "unspecified"))
      (node (ref "U21") (pin "10") (pinfunction "SCLR#_10") (pintype "unspecified"))
      (node (ref "U21") (pin "16") (pinfunction "VCC_16") (pintype "unspecified"))
    )
    (net (code "2") (name "A0") (class "Default")
      (node (ref "R5") (pin "1") (pinfunction "1_1") (pintype "unspecified"))
      (node (ref "U1") (pin "3") (pinfunction "3_3") (pintype "input"))
      (node (ref "U18") (pin "2") (pinfunction "I7_2") (pintype "unspecified"))
    )
    (net (code "3") (name "A1") (class "Default")
      (node (ref "R6") (pin "1") (pinfunction "1_1") (pintype "unspecified"))
      (node (ref "U18") (pin "3") (pinfunction "I6_3") (pintype "unspecified"))
      (node (ref "U2") (pin "3") (pinfunction "3_3") (pintype "input"))
    )
    (net (code "4") (name "A2") (class "Default")
      (node (ref "R7") (pin "1") (pinfunction "1_1") (pintype "unspecified"))
      (node (ref "U18") (pin "4") (pinfunction "I5_4") (pintype "unspecified"))
      (node (ref "U3") (pin "3") (pinfunction "3_3") (pintype "input"))
    )
    (net (code "5") (name "A3") (class "Default")
      (node (ref "R8") (pin "1") (pinfunction "1_1") (pintype "unspecified"))
      (node (ref "U18") (pin "5") (pinfunction "I4_5") (pintype "unspecified"))
      (node (ref "U4") (pin "3") (pinfunction "3_3") (pintype "input"))
    )
    (net (code "6") (name "A4") (class "Default")
      (node (ref "R13") (pin "1") (pinfunction "1_1") (pintype "unspecified"))
      (node (ref "U18") (pin "6") (pinfunction "I3_6") (pintype "unspecified"))
      (node (ref "U5") (pin "3") (pinfunction "3_3") (pintype "input"))
    )
    (net (code "7") (name "A5") (class "Default")
      (node (ref "R14") (pin "1") (pinfunction "1_1") (pintype "unspecified"))
      (node (ref "U18") (pin "7") (pinfunction "I2_7") (pintype "unspecified"))
      (node (ref "U6") (pin "3") (pinfunction "3_3") (pintype "input"))
    )
    (net (code "8") (name "A6") (class "Default")
      (node (ref "R15") (pin "1") (pinfunction "1_1") (pintype "unspecified"))
      (node (ref "U18") (pin "8") (pinfunction "I1_8") (pintype "unspecified"))
      (node (ref "U7") (pin "3") (pinfunction "3_3") (pintype "input"))
    )
    (net (code "9") (name "A7") (class "Default")
      (node (ref "R16") (pin "1") (pinfunction "1_1") (pintype "unspecified"))
      (node (ref "U18") (pin "9") (pinfunction "I0_9") (pintype "unspecified"))
      (node (ref "U8") (pin "3") (pinfunction "3_3") (pintype "input"))
    )
    (net (code "10") (name "A8") (class "Default")
      (node (ref "R21") (pin "1") (pinfunction "1_1") (pintype "unspecified"))
      (node (ref "U18") (pin "23") (pinfunction "I8_23") (pintype "unspecified"))
      (node (ref "U9") (pin "3") (pinfunction "3_3") (pintype "input"))
    )
    (net (code "11") (name "A9") (class "Default")
      (node (ref "R22") (pin "1") (pinfunction "1_1") (pintype "unspecified"))
      (node (ref "U10") (pin "3") (pinfunction "3_3") (pintype "input"))
      (node (ref "U18") (pin "22") (pinfunction "I9_22") (pintype "unspecified"))
    )
    (net (code "12") (name "A10") (class "Default")
      (node (ref "R23") (pin "1") (pinfunction "1_1") (pintype "unspecified"))
      (node (ref "U11") (pin "3") (pinfunction "3_3") (pintype "input"))
      (node (ref "U18") (pin "21") (pinfunction "I10_21") (pintype "unspecified"))
    )
    (net (code "13") (name "A11") (class "Default")
      (node (ref "R24") (pin "1") (pinfunction "1_1") (pintype "unspecified"))
      (node (ref "U12") (pin "3") (pinfunction "3_3") (pintype "input"))
      (node (ref "U18") (pin "20") (pinfunction "I11_20") (pintype "unspecified"))
    )
    (net (code "14") (name "A12") (class "Default")
      (node (ref "R29") (pin "1") (pinfunction "1_1") (pintype "unspecified"))
      (node (ref "U13") (pin "3") (pinfunction "3_3") (pintype "input"))
      (node (ref "U18") (pin "19") (pinfunction "I12_19") (pintype "unspecified"))
    )
    (net (code "15") (name "A13") (class "Default")
      (node (ref "R30") (pin "1") (pinfunction "1_1") (pintype "unspecified"))
      (node (ref "U14") (pin "3") (pinfunction "3_3") (pintype "input"))
      (node (ref "U18") (pin "18") (pinfunction "I13_18") (pintype "unspecified"))
    )
    (net (code "16") (name "A14") (class "Default")
      (node (ref "R31") (pin "1") (pinfunction "1_1") (pintype "unspecified"))
      (node (ref "U15") (pin "3") (pinfunction "3_3") (pintype "input"))
      (node (ref "U18") (pin "17") (pinfunction "I14_17") (pintype "unspecified"))
    )
    (net (code "17") (name "A15") (class "Default")
      (node (ref "R32") (pin "1") (pinfunction "1_1") (pintype "unspecified"))
      (node (ref "U16") (pin "3") (pinfunction "3_3") (pintype "input"))
      (node (ref "U18") (pin "16") (pinfunction "I15_16") (pintype "unspecified"))
    )
    (net (code "18") (name "ADC_IN0") (class "Default")
      (node (ref "U18") (pin "1") (pinfunction "COMMON_INPUT/OUTPUT_1") (pintype "unspecified"))
      (node (ref "U19") (pin "6") (pinfunction "PA0_6") (pintype "bidirectional"))
    )
    (net (code "19") (name "D_CK") (class "Default")
      (node (ref "U19") (pin "12") (pinfunction "PA6_12") (pintype "bidirectional"))
      (node (ref "U20") (pin "11") (pinfunction "SCK_11") (pintype "unspecified"))
      (node (ref "U21") (pin "11") (pinfunction "SCK_11") (pintype "unspecified"))
    )
    (net (code "20") (name "GND") (class "Default")
      (node (ref "C1") (pin "1") (pinfunction "1_1") (pintype "unspecified"))
      (node (ref "C2") (pin "1") (pinfunction "1_1") (pintype "unspecified"))
      (node (ref "C3") (pin "1") (pinfunction "1_1") (pintype "unspecified"))
      (node (ref "CN1") (pin "4") (pinfunction "4_4") (pintype "unspecified"))
      (node (ref "CN1") (pin "5") (pinfunction "5_5") (pintype "unspecified"))
      (node (ref "CN1") (pin "6") (pinfunction "6_6") (pintype "unspecified"))
      (node (ref "H1") (pin "1") (pinfunction "1_1") (pintype "unspecified"))
      (node (ref "JP1") (pin "2") (pinfunction "2_2") (pintype "unspecified"))
      (node (ref "JP2") (pin "2") (pinfunction "2_2") (pintype "unspecified"))
      (node (ref "LED1") (pin "2") (pinfunction "+_2") (pintype "input"))
      (node (ref "R53") (pin "1") (pinfunction "1_1") (pintype "unspecified"))
      (node (ref "U1") (pin "1") (pinfunction "1_1") (pintype "input"))
      (node (ref "U1") (pin "4") (pinfunction "4_4") (pintype "input"))
      (node (ref "U10") (pin "1") (pinfunction "1_1") (pintype "input"))
      (node (ref "U10") (pin "4") (pinfunction "4_4") (pintype "input"))
      (node (ref "U11") (pin "1") (pinfunction "1_1") (pintype "input"))
      (node (ref "U11") (pin "4") (pinfunction "4_4") (pintype "input"))
      (node (ref "U12") (pin "1") (pinfunction "1_1") (pintype "input"))
      (node (ref "U12") (pin "4") (pinfunction "4_4") (pintype "input"))
      (node (ref "U13") (pin "1") (pinfunction "1_1") (pintype "input"))
      (node (ref "U13") (pin "4") (pinfunction "4_4") (pintype "input"))
      (node (ref "U14") (pin "1") (pinfunction "1_1") (pintype "input"))
      (node (ref "U14") (pin "4") (pinfunction "4_4") (pintype "input"))
      (node (ref "U15") (pin "1") (pinfunction "1_1") (pintype "input"))
      (node (ref "U15") (pin "4") (pinfunction "4_4") (pintype "input"))
      (node (ref "U16") (pin "1") (pinfunction "1_1") (pintype "input"))
      (node (ref "U16") (pin "4") (pinfunction "4_4") (pintype "input"))
      (node (ref "U17") (pin "1") (pinfunction "VSS_1") (pintype "unspecified"))
      (node (ref "U18") (pin "12") (pinfunction "GND_12") (pintype "unspecified"))
      (node (ref "U18") (pin "15") (pinfunction "E#_15") (pintype "unspecified"))
      (node (ref "U19") (pin "15") (pinfunction "VSS_15") (pintype "unspecified"))
      (node (ref "U2") (pin "1") (pinfunction "1_1") (pintype "input"))
      (node (ref "U2") (pin "4") (pinfunction "4_4") (pintype "input"))
      (node (ref "U20") (pin "13") (pinfunction "G#_13") (pintype "unspecified"))
      (node (ref "U20") (pin "8") (pinfunction "GND_8") (pintype "unspecified"))
      (node (ref "U21") (pin "13") (pinfunction "G#_13") (pintype "unspecified"))
      (node (ref "U21") (pin "8") (pinfunction "GND_8") (pintype "unspecified"))
      (node (ref "U3") (pin "1") (pinfunction "1_1") (pintype "input"))
      (node (ref "U3") (pin "4") (pinfunction "4_4") (pintype "input"))
      (node (ref "U4") (pin "1") (pinfunction "1_1") (pintype "input"))
      (node (ref "U4") (pin "4") (pinfunction "4_4") (pintype "input"))
      (node (ref "U5") (pin "1") (pinfunction "1_1") (pintype "input"))
      (node (ref "U5") (pin "4") (pinfunction "4_4") (pintype "input"))
      (node (ref "U6") (pin "1") (pinfunction "1_1") (pintype "input"))
      (node (ref "U6") (pin "4") (pinfunction "4_4") (pintype "input"))
      (node (ref "U7") (pin "1") (pinfunction "1_1") (pintype "input"))
      (node (ref "U7") (pin "4") (pinfunction "4_4") (pintype "input"))
      (node (ref "U8") (pin "1") (pinfunction "1_1") (pintype "input"))
      (node (ref "U8") (pin "4") (pinfunction "4_4") (pintype "input"))
      (node (ref "U9") (pin "1") (pinfunction "1_1") (pintype "input"))
      (node (ref "U9") (pin "4") (pinfunction "4_4") (pintype "input"))
    )
    (net (code "21") (name "LED1") (class "Default")
      (node (ref "R34") (pin "2") (pinfunction "2_2") (pintype "input"))
      (node (ref "U20") (pin "15") (pinfunction "QA_15") (pintype "unspecified"))
    )
    (net (code "22") (name "LED2") (class "Default")
      (node (ref "R35") (pin "2") (pinfunction "2_2") (pintype "input"))
      (node (ref "U20") (pin "7") (pinfunction "QH_7") (pintype "unspecified"))
    )
    (net (code "23") (name "LED3") (class "Default")
      (node (ref "R36") (pin "2") (pinfunction "2_2") (pintype "input"))
      (node (ref "U20") (pin "6") (pinfunction "QG_6") (pintype "unspecified"))
    )
    (net (code "24") (name "LED4") (class "Default")
      (node (ref "R37") (pin "2") (pinfunction "2_2") (pintype "input"))
      (node (ref "U20") (pin "5") (pinfunction "QF_5") (pintype "unspecified"))
    )
    (net (code "25") (name "LED5") (class "Default")
      (node (ref "R38") (pin "2") (pinfunction "2_2") (pintype "input"))
      (node (ref "U20") (pin "4") (pinfunction "QE_4") (pintype "unspecified"))
    )
    (net (code "26") (name "LED6") (class "Default")
      (node (ref "R39") (pin "2") (pinfunction "2_2") (pintype "input"))
      (node (ref "U20") (pin "3") (pinfunction "QD_3") (pintype "unspecified"))
    )
    (net (code "27") (name "LED7") (class "Default")
      (node (ref "R40") (pin "2") (pinfunction "2_2") (pintype "input"))
      (node (ref "U20") (pin "2") (pinfunction "QC_2") (pintype "unspecified"))
    )
    (net (code "28") (name "LED8") (class "Default")
      (node (ref "R41") (pin "2") (pinfunction "2_2") (pintype "input"))
      (node (ref "U20") (pin "1") (pinfunction "QB_1") (pintype "unspecified"))
    )
    (net (code "29") (name "LED9") (class "Default")
      (node (ref "R42") (pin "2") (pinfunction "2_2") (pintype "input"))
      (node (ref "U21") (pin "15") (pinfunction "QA_15") (pintype "unspecified"))
    )
    (net (code "30") (name "LED10") (class "Default")
      (node (ref "R43") (pin "2") (pinfunction "2_2") (pintype "input"))
      (node (ref "U21") (pin "7") (pinfunction "QH_7") (pintype "unspecified"))
    )
    (net (code "31") (name "LED11") (class "Default")
      (node (ref "R44") (pin "2") (pinfunction "2_2") (pintype "input"))
      (node (ref "U21") (pin "6") (pinfunction "QG_6") (pintype "unspecified"))
    )
    (net (code "32") (name "LED12") (class "Default")
      (node (ref "R45") (pin "2") (pinfunction "2_2") (pintype "input"))
      (node (ref "U21") (pin "5") (pinfunction "QF_5") (pintype "unspecified"))
    )
    (net (code "33") (name "LED13") (class "Default")
      (node (ref "R46") (pin "2") (pinfunction "2_2") (pintype "input"))
      (node (ref "U21") (pin "4") (pinfunction "QE_4") (pintype "unspecified"))
    )
    (net (code "34") (name "LED14") (class "Default")
      (node (ref "R47") (pin "2") (pinfunction "2_2") (pintype "input"))
      (node (ref "U21") (pin "3") (pinfunction "QD_3") (pintype "unspecified"))
    )
    (net (code "35") (name "LED15") (class "Default")
      (node (ref "R48") (pin "1") (pinfunction "1_1") (pintype "input"))
      (node (ref "U21") (pin "2") (pinfunction "QC_2") (pintype "unspecified"))
    )
    (net (code "36") (name "LED16") (class "Default")
      (node (ref "R49") (pin "2") (pinfunction "2_2") (pintype "input"))
      (node (ref "U21") (pin "1") (pinfunction "QB_1") (pintype "unspecified"))
    )
    (net (code "37") (name "LEDS") (class "Default")
      (node (ref "U19") (pin "14") (pinfunction "PB1_14") (pintype "bidirectional"))
      (node (ref "U20") (pin "14") (pinfunction "SER_14") (pintype "unspecified"))
    )
    (net (code "38") (name "L_CK") (class "Default")
      (node (ref "U19") (pin "13") (pinfunction "PA7_13") (pintype "bidirectional"))
      (node (ref "U20") (pin "12") (pinfunction "RCK_12") (pintype "unspecified"))
      (node (ref "U21") (pin "12") (pinfunction "RCK_12") (pintype "unspecified"))
    )
    (net (code "39") (name "MUX_0") (class "Default")
      (node (ref "U18") (pin "10") (pinfunction "S0_10") (pintype "unspecified"))
      (node (ref "U19") (pin "7") (pinfunction "PA1_7") (pintype "bidirectional"))
    )
    (net (code "40") (name "MUX_1") (class "Default")
      (node (ref "U18") (pin "11") (pinfunction "S1_11") (pintype "unspecified"))
      (node (ref "U19") (pin "8") (pinfunction "PA2_8") (pintype "bidirectional"))
    )
    (net (code "41") (name "MUX_2") (class "Default")
      (node (ref "U18") (pin "14") (pinfunction "S2_14") (pintype "unspecified"))
      (node (ref "U19") (pin "9") (pinfunction "PA3_9") (pintype "bidirectional"))
    )
    (net (code "42") (name "MUX_3") (class "Default")
      (node (ref "U18") (pin "13") (pinfunction "S3_13") (pintype "unspecified"))
      (node (ref "U19") (pin "10") (pinfunction "PA4_10") (pintype "bidirectional"))
    )
    (net (code "43") (name "Net-(LED1--)") (class "Default")
      (node (ref "LED1") (pin "1") (pinfunction "-_1") (pintype "input"))
      (node (ref "R33") (pin "1") (pinfunction "1_1") (pintype "input"))
    )
    (net (code "44") (name "Net-(LED2--)") (class "Default")
      (node (ref "LED2") (pin "1") (pinfunction "-_1") (pintype "input"))
      (node (ref "R34") (pin "1") (pinfunction "1_1") (pintype "input"))
    )
    (net (code "45") (name "Net-(LED3--)") (class "Default")
      (node (ref "LED3") (pin "1") (pinfunction "-_1") (pintype "input"))
      (node (ref "R35") (pin "1") (pinfunction "1_1") (pintype "input"))
    )
    (net (code "46") (name "Net-(LED4--)") (class "Default")
      (node (ref "LED4") (pin "1") (pinfunction "-_1") (pintype "input"))
      (node (ref "R36") (pin "1") (pinfunction "1_1") (pintype "input"))
    )
    (net (code "47") (name "Net-(LED5--)") (class "Default")
      (node (ref "LED5") (pin "1") (pinfunction "-_1") (pintype "input"))
      (node (ref "R37") (pin "1") (pinfunction "1_1") (pintype "input"))
    )
    (net (code "48") (name "Net-(LED6--)") (class "Default")
      (node (ref "LED6") (pin "1") (pinfunction "-_1") (pintype "input"))
      (node (ref "R38") (pin "1") (pinfunction "1_1") (pintype "input"))
    )
    (net (code "49") (name "Net-(LED7--)") (class "Default")
      (node (ref "LED7") (pin "1") (pinfunction "-_1") (pintype "input"))
      (node (ref "R39") (pin "1") (pinfunction "1_1") (pintype "input"))
    )
    (net (code "50") (name "Net-(LED8--)") (class "Default")
      (node (ref "LED8") (pin "1") (pinfunction "-_1") (pintype "input"))
      (node (ref "R40") (pin "1") (pinfunction "1_1") (pintype "input"))
    )
    (net (code "51") (name "Net-(LED9--)") (class "Default")
      (node (ref "LED9") (pin "1") (pinfunction "-_1") (pintype "input"))
      (node (ref "R41") (pin "1") (pinfunction "1_1") (pintype "input"))
    )
    (net (code "52") (name "Net-(LED10--)") (class "Default")
      (node (ref "LED10") (pin "1") (pinfunction "-_1") (pintype "input"))
      (node (ref "R42") (pin "1") (pinfunction "1_1") (pintype "input"))
    )
    (net (code "53") (name "Net-(LED11--)") (class "Default")
      (node (ref "LED11") (pin "1") (pinfunction "-_1") (pintype "input"))
      (node (ref "R43") (pin "1") (pinfunction "1_1") (pintype "input"))
    )
    (net (code "54") (name "Net-(LED12--)") (class "Default")
      (node (ref "LED12") (pin "1") (pinfunction "-_1") (pintype "input"))
      (node (ref "R44") (pin "1") (pinfunction "1_1") (pintype "input"))
    )
    (net (code "55") (name "Net-(LED13--)") (class "Default")
      (node (ref "LED13") (pin "1") (pinfunction "-_1") (pintype "input"))
      (node (ref "R45") (pin "1") (pinfunction "1_1") (pintype "input"))
    )
    (net (code "56") (name "Net-(LED14--)") (class "Default")
      (node (ref "LED14") (pin "1") (pinfunction "-_1") (pintype "input"))
      (node (ref "R46") (pin "1") (pinfunction "1_1") (pintype "input"))
    )
    (net (code "57") (name "Net-(LED15--)") (class "Default")
      (node (ref "LED15") (pin "1") (pinfunction "-_1") (pintype "input"))
      (node (ref "R47") (pin "1") (pinfunction "1_1") (pintype "input"))
    )
    (net (code "58") (name "Net-(LED16--)") (class "Default")
      (node (ref "LED16") (pin "1") (pinfunction "-_1") (pintype "input"))
      (node (ref "R48") (pin "2") (pinfunction "2_2") (pintype "input"))
    )
    (net (code "59") (name "Net-(LED17--)") (class "Default")
      (node (ref "LED17") (pin "1") (pinfunction "-_1") (pintype "input"))
      (node (ref "R49") (pin "1") (pinfunction "1_1") (pintype "input"))
    )
    (net (code "60") (name "Net-(R1-Pad2)") (class "Default")
      (node (ref "R1") (pin "2") (pinfunction "2_2") (pintype "unspecified"))
      (node (ref "U1") (pin "2") (pinfunction "2_2") (pintype "input"))
    )
    (net (code "61") (name "Net-(R2-Pad2)") (class "Default")
      (node (ref "R2") (pin "2") (pinfunction "2_2") (pintype "unspecified"))
      (node (ref "U2") (pin "2") (pinfunction "2_2") (pintype "input"))
    )
    (net (code "62") (name "Net-(R3-Pad2)") (class "Default")
      (node (ref "R3") (pin "2") (pinfunction "2_2") (pintype "unspecified"))
      (node (ref "U3") (pin "2") (pinfunction "2_2") (pintype "input"))
    )
    (net (code "63") (name "Net-(R4-Pad2)") (class "Default")
      (node (ref "R4") (pin "2") (pinfunction "2_2") (pintype "unspecified"))
      (node (ref "U4") (pin "2") (pinfunction "2_2") (pintype "input"))
    )
    (net (code "64") (name "Net-(R9-Pad2)") (class "Default")
      (node (ref "R9") (pin "2") (pinfunction "2_2") (pintype "unspecified"))
      (node (ref "U5") (pin "2") (pinfunction "2_2") (pintype "input"))
    )
    (net (code "65") (name "Net-(R10-Pad2)") (class "Default")
      (node (ref "R10") (pin "2") (pinfunction "2_2") (pintype "unspecified"))
      (node (ref "U6") (pin "2") (pinfunction "2_2") (pintype "input"))
    )
    (net (code "66") (name "Net-(R11-Pad2)") (class "Default")
      (node (ref "R11") (pin "2") (pinfunction "2_2") (pintype "unspecified"))
      (node (ref "U7") (pin "2") (pinfunction "2_2") (pintype "input"))
    )
    (net (code "67") (name "Net-(R12-Pad2)") (class "Default")
      (node (ref "R12") (pin "2") (pinfunction "2_2") (pintype "unspecified"))
      (node (ref "U8") (pin "2") (pinfunction "2_2") (pintype "input"))
    )
    (net (code "68") (name "Net-(R17-Pad2)") (class "Default")
      (node (ref "R17") (pin "2") (pinfunction "2_2") (pintype "unspecified"))
      (node (ref "U9") (pin "2") (pinfunction "2_2") (pintype "input"))
    )
    (net (code "69") (name "Net-(R18-Pad2)") (class "Default")
      (node (ref "R18") (pin "2") (pinfunction "2_2") (pintype "unspecified"))
      (node (ref "U10") (pin "2") (pinfunction "2_2") (pintype "input"))
    )
    (net (code "70") (name "Net-(R19-Pad2)") (class "Default")
      (node (ref "R19") (pin "2") (pinfunction "2_2") (pintype "unspecified"))
      (node (ref "U11") (pin "2") (pinfunction "2_2") (pintype "input"))
    )
    (net (code "71") (name "Net-(R20-Pad2)") (class "Default")
      (node (ref "R20") (pin "2") (pinfunction "2_2") (pintype "unspecified"))
      (node (ref "U12") (pin "2") (pinfunction "2_2") (pintype "input"))
    )
    (net (code "72") (name "Net-(R25-Pad2)") (class "Default")
      (node (ref "R25") (pin "2") (pinfunction "2_2") (pintype "unspecified"))
      (node (ref "U13") (pin "2") (pinfunction "2_2") (pintype "input"))
    )
    (net (code "73") (name "Net-(R26-Pad2)") (class "Default")
      (node (ref "R26") (pin "2") (pinfunction "2_2") (pintype "unspecified"))
      (node (ref "U14") (pin "2") (pinfunction "2_2") (pintype "input"))
    )
    (net (code "74") (name "Net-(R27-Pad2)") (class "Default")
      (node (ref "R27") (pin "2") (pinfunction "2_2") (pintype "unspecified"))
      (node (ref "U15") (pin "2") (pinfunction "2_2") (pintype "input"))
    )
    (net (code "75") (name "Net-(R28-Pad2)") (class "Default")
      (node (ref "R28") (pin "2") (pinfunction "2_2") (pintype "unspecified"))
      (node (ref "U16") (pin "2") (pinfunction "2_2") (pintype "input"))
    )
    (net (code "76") (name "Net-(U19-BOOT0)") (class "Default")
      (node (ref "R53") (pin "2") (pinfunction "2_2") (pintype "unspecified"))
      (node (ref "U19") (pin "1") (pinfunction "BOOT0_1") (pintype "unspecified"))
    )
    (net (code "77") (name "Net-(U19-NRST)") (class "Default")
      (node (ref "C3") (pin "2") (pinfunction "2_2") (pintype "unspecified"))
      (node (ref "R50") (pin "1") (pinfunction "1_1") (pintype "unspecified"))
      (node (ref "U19") (pin "4") (pinfunction "NRST_4") (pintype "bidirectional"))
    )
    (net (code "78") (name "Net-(U19-PA5)") (class "Default")
      (node (ref "R33") (pin "2") (pinfunction "2_2") (pintype "input"))
      (node (ref "U19") (pin "11") (pinfunction "PA5_11") (pintype "bidirectional"))
    )
    (net (code "79") (name "Net-(U19-PA13(SWDIO))") (class "Default")
      (node (ref "SWD") (pin "1") (pinfunction "1_1") (pintype "unspecified"))
      (node (ref "U19") (pin "19") (pinfunction "PA13(SWDIO)_19") (pintype "bidirectional"))
    )
    (net (code "80") (name "Net-(U19-PA14(SWCLK))") (class "Default")
      (node (ref "CLK") (pin "1") (pinfunction "1_1") (pintype "unspecified"))
      (node (ref "U19") (pin "20") (pinfunction "PA14(SWCLK)_20") (pintype "bidirectional"))
    )
    (net (code "81") (name "Net-(U19-PF0-OSC_IN(PF0))") (class "Default")
      (node (ref "JP1") (pin "1") (pinfunction "1_1") (pintype "unspecified"))
      (node (ref "U19") (pin "2") (pinfunction "PF0-OSC_IN(PF0)_2") (pintype "bidirectional"))
    )
    (net (code "82") (name "Net-(U19-PF1-OSC_OUT(PF1))") (class "Default")
      (node (ref "JP2") (pin "1") (pinfunction "1_1") (pintype "unspecified"))
      (node (ref "U19") (pin "3") (pinfunction "PF1-OSC_OUT(PF1)_3") (pintype "bidirectional"))
    )
    (net (code "83") (name "Net-(U20-Q′H)") (class "Default")
      (node (ref "U20") (pin "9") (pinfunction "Q′H_9") (pintype "unspecified"))
      (node (ref "U21") (pin "14") (pinfunction "SER_14") (pintype "unspecified"))
    )
    (net (code "84") (name "SCL") (class "Default")
      (node (ref "CN1") (pin "1") (pinfunction "1_1") (pintype "unspecified"))
      (node (ref "H1") (pin "3") (pinfunction "3_3") (pintype "unspecified"))
      (node (ref "R51") (pin "1") (pinfunction "1_1") (pintype "input"))
      (node (ref "U19") (pin "17") (pinfunction "PA9_17") (pintype "bidirectional"))
    )
    (net (code "85") (name "SDA") (class "Default")
      (node (ref "CN1") (pin "2") (pinfunction "2_2") (pintype "unspecified"))
      (node (ref "H1") (pin "2") (pinfunction "2_2") (pintype "unspecified"))
      (node (ref "R52") (pin "1") (pinfunction "1_1") (pintype "input"))
      (node (ref "U19") (pin "18") (pinfunction "PA10_18") (pintype "bidirectional"))
    )
    (net (code "86") (name "VCC") (class "Default")
      (node (ref "C2") (pin "2") (pinfunction "2_2") (pintype "unspecified"))
      (node (ref "CN1") (pin "3") (pinfunction "3_3") (pintype "unspecified"))
      (node (ref "H1") (pin "4") (pinfunction "4_4") (pintype "unspecified"))
      (node (ref "R1") (pin "1") (pinfunction "1_1") (pintype "unspecified"))
      (node (ref "R10") (pin "1") (pinfunction "1_1") (pintype "unspecified"))
      (node (ref "R11") (pin "1") (pinfunction "1_1") (pintype "unspecified"))
      (node (ref "R12") (pin "1") (pinfunction "1_1") (pintype "unspecified"))
      (node (ref "R17") (pin "1") (pinfunction "1_1") (pintype "unspecified"))
      (node (ref "R18") (pin "1") (pinfunction "1_1") (pintype "unspecified"))
      (node (ref "R19") (pin "1") (pinfunction "1_1") (pintype "unspecified"))
      (node (ref "R2") (pin "1") (pinfunction "1_1") (pintype "unspecified"))
      (node (ref "R20") (pin "1") (pinfunction "1_1") (pintype "unspecified"))
      (node (ref "R25") (pin "1") (pinfunction "1_1") (pintype "unspecified"))
      (node (ref "R26") (pin "1") (pinfunction "1_1") (pintype "unspecified"))
      (node (ref "R27") (pin "1") (pinfunction "1_1") (pintype "unspecified"))
      (node (ref "R28") (pin "1") (pinfunction "1_1") (pintype "unspecified"))
      (node (ref "R3") (pin "1") (pinfunction "1_1") (pintype "unspecified"))
      (node (ref "R4") (pin "1") (pinfunction "1_1") (pintype "unspecified"))
      (node (ref "R51") (pin "2") (pinfunction "2_2") (pintype "input"))
      (node (ref "R52") (pin "2") (pinfunction "2_2") (pintype "input"))
      (node (ref "R9") (pin "1") (pinfunction "1_1") (pintype "unspecified"))
      (node (ref "U17") (pin "3") (pinfunction "VIN_3") (pintype "unspecified"))
    )
    (net (code "87") (name "unconnected-(SCREW1-Pad1)") (class "Default")
      (node (ref "SCREW1") (pin "1") (pinfunction "1_1") (pintype "input+no_connect"))
    )
    (net (code "88") (name "unconnected-(SCREW2-Pad1)") (class "Default")
      (node (ref "SCREW2") (pin "1") (pinfunction "1_1") (pintype "input+no_connect"))
    )
    (net (code "89") (name "unconnected-(SCREW3-Pad1)") (class "Default")
      (node (ref "SCREW3") (pin "1") (pinfunction "1_1") (pintype "input+no_connect"))
    )
    (net (code "90") (name "unconnected-(SCREW4-Pad1)") (class "Default")
      (node (ref "SCREW4") (pin "1") (pinfunction "1_1") (pintype "input+no_connect"))
    )
    (net (code "91") (name "unconnected-(U21-Q′H-Pad9)") (class "Default")
      (node (ref "U21") (pin "9") (pinfunction "Q′H_9") (pintype "unspecified+no_connect"))
    )
  )
)
